# STS30.net
KiCad netlist of a schematic drawn in Altium Designer
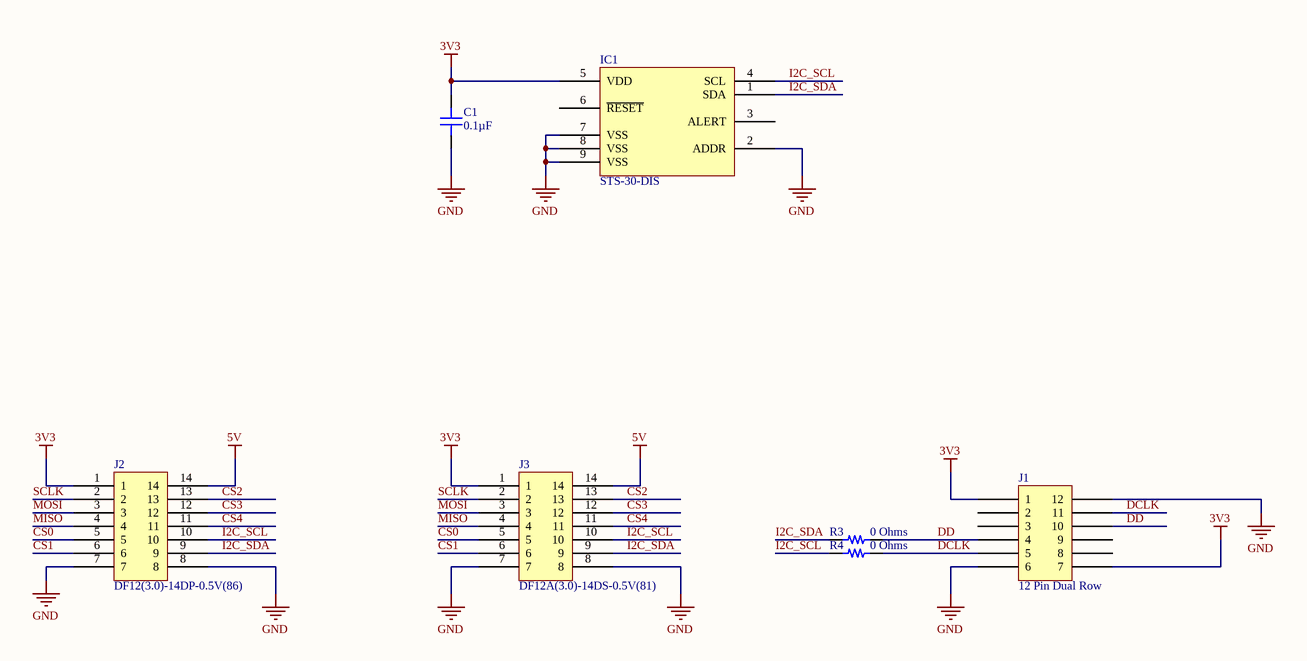
[diagram p0: STS30.SchDoc]

(export (version "E")
  (design (tool "Eeschema 10.0.6"))
  (components
    (comp (ref "C1")
      (value "0.1µF")
      (footprint "CAP 0603_1608")
      (description "CAP CER 0.1UF 16V Y5V 0603")
      (fields (field (name "PART NUMBER") "CC0603ZRY5V7BB104") (field (name "MANUFACTURER") "Yageo"))
      (libsource (lib "altiumlibrary.com") (part "Capacitor"))
    )
    (comp (ref "IC1")
      (value "STS-30-DIS")
      (footprint "SENSIRION STS-30-DIS")
      (description "SENSOR DIGITAL 0C-65C 8TDFN")
      (fields (field (name "MANUFACTURER") "Sensirion AG"))
      (libsource (lib "altiumlibrary.com") (part "Sensirion STS-30-DIS"))
    )
    (comp (ref "J1")
      (value "12 Pin Dual Row")
      (footprint "TE 5650118-3 Card Edge")
      (libsource (lib "CelestialUseful") (part "12 Pin Dual Row"))
    )
    (comp (ref "J2")
      (value "DF12(3.0)-14DP-0.5V(86)")
      (footprint "HIROSE DF12 3.0-14DP-0.5V 86")
      (description "CONN HDR 14POS SMD GOLD")
      (fields (field (name "MANUFACTURER") "Hirose Electric Co Ltd"))
      (libsource (lib "altiumlibrary.com") (part "14 Pin Dual Row"))
    )
    (comp (ref "J3")
      (value "DF12A(3.0)-14DS-0.5V(81)")
      (footprint "HIROSE DF12A 3.0-14DS-0.5V 81")
      (description "CONN RCPT 14POS SMD GOLD")
      (fields (field (name "MANUFACTURER") "Hirose Electric Co Ltd"))
      (libsource (lib "altiumlibrary.com") (part "14 Pin Dual Row"))
    )
    (comp (ref "R3")
      (value "0 Ohms")
      (footprint "RES 0603_1608")
      (description "RES SMD 0 OHM JUMPER 1/10W 0603")
      (fields
        (field (name "PART NUMBER") "ERJ-3GEY0R00V")
        (field (name "MANUFACTURER") "Panasonic Electronic Components")
      )
      (libsource (lib "altiumlibrary.com") (part "Resistor"))
    )
    (comp (ref "R4")
      (value "0 Ohms")
      (footprint "RES 0603_1608")
      (description "RES SMD 0 OHM JUMPER 1/10W 0603")
      (fields
        (field (name "PART NUMBER") "ERJ-3GEY0R00V")
        (field (name "MANUFACTURER") "Panasonic Electronic Components")
      )
      (libsource (lib "altiumlibrary.com") (part "Resistor"))
    )
  )
  (nets
    (net (code "1") (name "/CS0") (class "Default")
      (node (ref "J2") (pin "5") (pinfunction "5_5") (pintype "passive"))
      (node (ref "J3") (pin "5") (pinfunction "5_5") (pintype "passive"))
    )
    (net (code "2") (name "/CS1") (class "Default")
      (node (ref "J2") (pin "6") (pinfunction "6_6") (pintype "passive"))
      (node (ref "J3") (pin "6") (pinfunction "6_6") (pintype "passive"))
    )
    (net (code "3") (name "/CS2") (class "Default")
      (node (ref "J2") (pin "13") (pinfunction "13_13") (pintype "passive"))
      (node (ref "J3") (pin "13") (pinfunction "13_13") (pintype "passive"))
    )
    (net (code "4") (name "/CS3") (class "Default")
      (node (ref "J2") (pin "12") (pinfunction "12_12") (pintype "passive"))
      (node (ref "J3") (pin "12") (pinfunction "12_12") (pintype "passive"))
    )
    (net (code "5") (name "/CS4") (class "Default")
      (node (ref "J2") (pin "11") (pinfunction "11_11") (pintype "passive"))
      (node (ref "J3") (pin "11") (pinfunction "11_11") (pintype "passive"))
    )
    (net (code "6") (name "/DCLK") (class "Default")
      (node (ref "J1") (pin "11") (pinfunction "11_11") (pintype "passive"))
      (node (ref "J1") (pin "5") (pinfunction "5_5") (pintype "passive"))
      (node (ref "R4") (pin "2") (pinfunction "2_2") (pintype "passive"))
    )
    (net (code "7") (name "/DD") (class "Default")
      (node (ref "J1") (pin "10") (pinfunction "10_10") (pintype "passive"))
      (node (ref "J1") (pin "4") (pinfunction "4_4") (pintype "passive"))
      (node (ref "R3") (pin "2") (pinfunction "2_2") (pintype "passive"))
    )
    (net (code "8") (name "/I2C_SCL") (class "Default")
      (node (ref "IC1") (pin "4") (pinfunction "SCL_4") (pintype "passive"))
      (node (ref "J2") (pin "10") (pinfunction "10_10") (pintype "passive"))
      (node (ref "J3") (pin "10") (pinfunction "10_10") (pintype "passive"))
      (node (ref "R4") (pin "1") (pinfunction "1_1") (pintype "passive"))
    )
    (net (code "9") (name "/I2C_SDA") (class "Default")
      (node (ref "IC1") (pin "1") (pinfunction "SDA_1") (pintype "passive"))
      (node (ref "J2") (pin "9") (pinfunction "9_9") (pintype "passive"))
      (node (ref "J3") (pin "9") (pinfunction "9_9") (pintype "passive"))
      (node (ref "R3") (pin "1") (pinfunction "1_1") (pintype "passive"))
    )
    (net (code "10") (name "/MISO") (class "Default")
      (node (ref "J2") (pin "4") (pinfunction "4_4") (pintype "passive"))
      (node (ref "J3") (pin "4") (pinfunction "4_4") (pintype "passive"))
    )
    (net (code "11") (name "/MOSI") (class "Default")
      (node (ref "J2") (pin "3") (pinfunction "3_3") (pintype "passive"))
      (node (ref "J3") (pin "3") (pinfunction "3_3") (pintype "passive"))
    )
    (net (code "12") (name "/SCLK") (class "Default")
      (node (ref "J2") (pin "2") (pinfunction "2_2") (pintype "passive"))
      (node (ref "J3") (pin "2") (pinfunction "2_2") (pintype "passive"))
    )
    (net (code "13") (name "3V3") (class "Default")
      (node (ref "C1") (pin "1") (pinfunction "1_1") (pintype "passive"))
      (node (ref "IC1") (pin "5") (pinfunction "VDD_5") (pintype "passive"))
      (node (ref "J1") (pin "1") (pinfunction "1_1") (pintype "passive"))
      (node (ref "J1") (pin "7") (pinfunction "7_7") (pintype "passive"))
      (node (ref "J2") (pin "1") (pinfunction "1_1") (pintype "passive"))
      (node (ref "J3") (pin "1") (pinfunction "1_1") (pintype "passive"))
    )
    (net (code "14") (name "5V") (class "Default")
      (node (ref "J2") (pin "14") (pinfunction "14_14") (pintype "passive"))
      (node (ref "J3") (pin "14") (pinfunction "14_14") (pintype "passive"))
    )
    (net (code "15") (name "GND") (class "Default")
      (node (ref "C1") (pin "2") (pinfunction "2_2") (pintype "passive"))
      (node (ref "IC1") (pin "2") (pinfunction "ADDR_2") (pintype "passive"))
      (node (ref "IC1") (pin "7") (pinfunction "VSS_7") (pintype "passive"))
      (node (ref "IC1") (pin "8") (pinfunction "VSS_8") (pintype "passive"))
      (node (ref "IC1") (pin "9") (pinfunction "VSS_9") (pintype "passive"))
      (node (ref "J1") (pin "12") (pinfunction "12_12") (pintype "passive"))
      (node (ref "J1") (pin "6") (pinfunction "6_6") (pintype "passive"))
      (node (ref "J2") (pin "7") (pinfunction "7_7") (pintype "passive"))
      (node (ref "J2") (pin "8") (pinfunction "8_8") (pintype "passive"))
      (node (ref "J3") (pin "7") (pinfunction "7_7") (pintype "passive"))
      (node (ref "J3") (pin "8") (pinfunction "8_8") (pintype "passive"))
    )
    (net (code "16") (name "unconnected-(IC1-ALERT-Pad3)") (class "Default")
      (node (ref "IC1") (pin "3") (pinfunction "ALERT_3") (pintype "passive"))
    )
    (net (code "17") (name "unconnected-(IC1-~{RESET}-Pad6)") (class "Default")
      (node (ref "IC1") (pin "6") (pinfunction "~{RESET}_6") (pintype "passive"))
    )
    (net (code "18") (name "unconnected-(J1-Pad2)") (class "Default")
      (node (ref "J1") (pin "2") (pinfunction "2_2") (pintype "passive"))
    )
    (net (code "19") (name "unconnected-(J1-Pad3)") (class "Default")
      (node (ref "J1") (pin "3") (pinfunction "3_3") (pintype "passive"))
    )
    (net (code "20") (name "unconnected-(J1-Pad8)") (class "Default")
      (node (ref "J1") (pin "8") (pinfunction "8_8") (pintype "passive"))
    )
    (net (code "21") (name "unconnected-(J1-Pad9)") (class "Default")
      (node (ref "J1") (pin "9") (pinfunction "9_9") (pintype "passive"))
    )
  )
)
